# output.net
KiCad netlist of a schematic drawn in Altium Designer
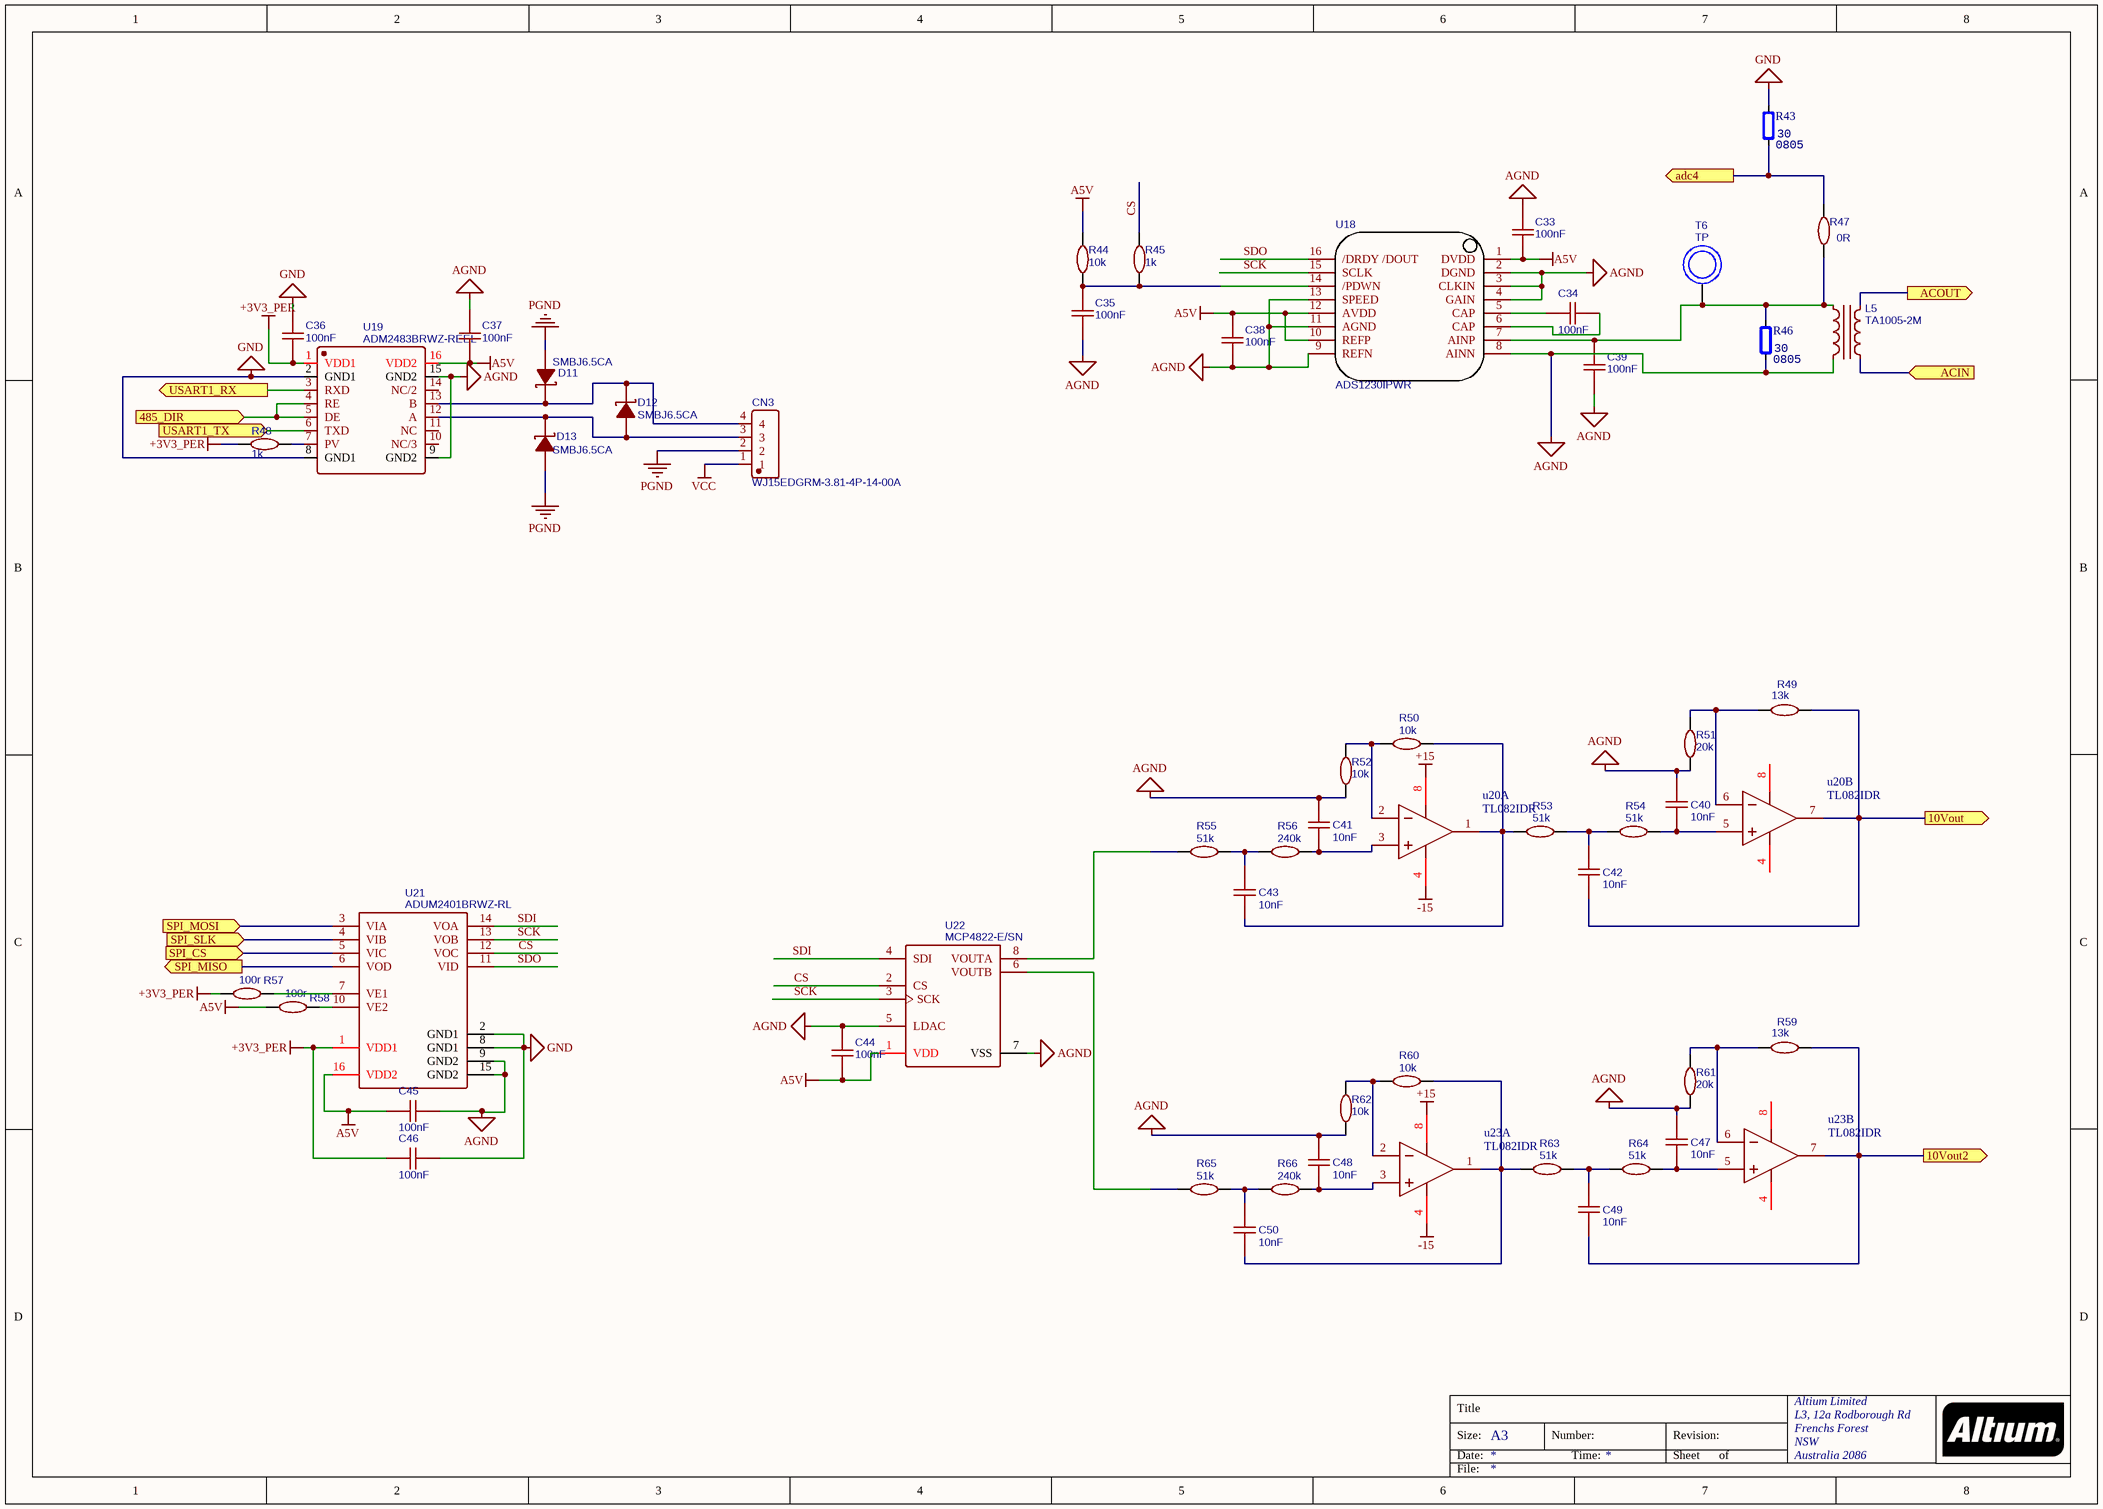
[diagram p0: output.SchDoc]

(export (version "E")
  (design (tool "Eeschema 10.0.6"))
  (components
    (comp (ref "C33")
      (value "100nF")
      (footprint "0603 - cap")
      (fields (field (name "BOM_MANUFACTURER PART") "CC0603KRX7R9BB104"))
      (libsource (lib "") (part "root_3___1"))
    )
    (comp (ref "C34")
      (value "100nF")
      (footprint "0603 - cap")
      (fields (field (name "BOM_MANUFACTURER PART") "CC0603KRX7R9BB104"))
      (libsource (lib "") (part "root_0___4"))
    )
    (comp (ref "C35")
      (value "100nF")
      (footprint "0603 - cap")
      (fields (field (name "BOM_MANUFACTURER PART") "CC0603KRX7R9BB104"))
      (libsource (lib "") (part "root_3___1"))
    )
    (comp (ref "C36")
      (value "100nF")
      (footprint "0603 - cap")
      (fields (field (name "BOM_MANUFACTURER PART") "CC0603KRX7R9BB104"))
      (libsource (lib "") (part "root_3___1"))
    )
    (comp (ref "C37")
      (value "100nF")
      (footprint "0603 - cap")
      (fields (field (name "BOM_MANUFACTURER PART") "CC0603KRX7R9BB104"))
      (libsource (lib "") (part "root_3___1"))
    )
    (comp (ref "C38")
      (value "100nF")
      (footprint "0603 - cap")
      (fields (field (name "BOM_MANUFACTURER PART") "CC0603KRX7R9BB104"))
      (libsource (lib "") (part "root_3___1"))
    )
    (comp (ref "C39")
      (value "100nF")
      (footprint "0603 - cap")
      (fields (field (name "BOM_MANUFACTURER PART") "CC0603KRX7R9BB104"))
      (libsource (lib "") (part "root_3___1"))
    )
    (comp (ref "C40")
      (value "10nF")
      (footprint "0603 - cap")
      (fields (field (name "BOM_MANUFACTURER PART") "CC0603KRX7R9BB104"))
      (libsource (lib "") (part "root_1___1"))
    )
    (comp (ref "C41")
      (value "10nF")
      (footprint "0603 - cap")
      (fields (field (name "BOM_MANUFACTURER PART") "CC0603KRX7R9BB104"))
      (libsource (lib "") (part "root_1___1"))
    )
    (comp (ref "C42")
      (value "10nF")
      (footprint "0603 - cap")
      (fields (field (name "BOM_MANUFACTURER PART") "CC0603KRX7R9BB104"))
      (libsource (lib "") (part "root_1___1"))
    )
    (comp (ref "C43")
      (value "10nF")
      (footprint "0603 - cap")
      (fields (field (name "BOM_MANUFACTURER PART") "CC0603KRX7R9BB104"))
      (libsource (lib "") (part "root_1___1"))
    )
    (comp (ref "C44")
      (value "100nF")
      (footprint "0603 - cap")
      (fields (field (name "BOM_MANUFACTURER PART") "CC0603KRX7R9BB104"))
      (libsource (lib "") (part "root_3___1"))
    )
    (comp (ref "C45")
      (value "100nF")
      (footprint "0603 - cap")
      (fields (field (name "BOM_MANUFACTURER PART") "CC0603KRX7R9BB104"))
      (libsource (lib "altium-import") (part "root_2__"))
    )
    (comp (ref "C46")
      (value "100nF")
      (footprint "0603 - cap")
      (fields (field (name "BOM_MANUFACTURER PART") "CC0603KRX7R9BB104"))
      (libsource (lib "altium-import") (part "root_2__"))
    )
    (comp (ref "C47")
      (value "10nF")
      (footprint "0603 - cap")
      (fields (field (name "BOM_MANUFACTURER PART") "CC0603KRX7R9BB104"))
      (libsource (lib "") (part "root_1___1"))
    )
    (comp (ref "C48")
      (value "10nF")
      (footprint "0603 - cap")
      (fields (field (name "BOM_MANUFACTURER PART") "CC0603KRX7R9BB104"))
      (libsource (lib "") (part "root_1___1"))
    )
    (comp (ref "C49")
      (value "10nF")
      (footprint "0603 - cap")
      (fields (field (name "BOM_MANUFACTURER PART") "CC0603KRX7R9BB104"))
      (libsource (lib "") (part "root_1___1"))
    )
    (comp (ref "C50")
      (value "10nF")
      (footprint "0603 - cap")
      (fields (field (name "BOM_MANUFACTURER PART") "CC0603KRX7R9BB104"))
      (libsource (lib "") (part "root_1___1"))
    )
    (comp (ref "CN3")
      (value "WJ15EDGRM-3.81-4P-14-00A")
      (footprint "3.84-4p")
      (fields (field (name "CONTRIBUTOR") "LCSC"))
      (libsource (lib "altium-import") (part "root_2_mirrored__"))
    )
    (comp (ref "D11")
      (value "SMBJ6.5CA")
      (footprint "SMB(DO-214AA)")
      (libsource (lib "") (part "root_1___2"))
    )
    (comp (ref "D12")
      (value "SMBJ6.5CA")
      (footprint "SMB(DO-214AA)")
      (libsource (lib "altium-import") (part "root_3__"))
    )
    (comp (ref "D13")
      (value "SMBJ6.5CA")
      (footprint "SMB(DO-214AA)")
      (libsource (lib "altium-import") (part "root_3__"))
    )
    (comp (ref "L5") (value "TA1005-2M") (footprint "TA1005-2M") (libsource (lib "") (part "root_3___2")))
    (comp (ref "R43")
      (value "30")
      (footprint "PCB_PassiveRes:RES_0805")
      (description "Resistor")
      (fields (field (name "TYPE") "0805") (field (name "Comment") "R0805"))
      (libsource (lib "SCH_Passive") (part "Res_0805"))
    )
    (comp (ref "R44")
      (value "10k")
      (footprint "0603-res")
      (fields (field (name "BOM_MANUFACTURER PART") "0603WAF1001T5E"))
      (libsource (lib "altium-import") (part "root_1__"))
    )
    (comp (ref "R45")
      (value "1k")
      (footprint "0603-res")
      (fields (field (name "BOM_MANUFACTURER PART") "0603WAF1001T5E"))
      (libsource (lib "altium-import") (part "root_1__"))
    )
    (comp (ref "R46")
      (value "30")
      (footprint "PCB_PassiveRes:RES_0805")
      (description "Resistor")
      (fields (field (name "TYPE") "0805") (field (name "Comment") "R0805"))
      (libsource (lib "SCH_Passive") (part "Res_0805"))
    )
    (comp (ref "R47")
      (value "0R")
      (footprint "0603-res")
      (fields (field (name "BOM_MANUFACTURER PART") "0603WAF1001T5E"))
      (libsource (lib "altium-import") (part "root_1__"))
    )
    (comp (ref "R48")
      (value "1k")
      (footprint "0603-res")
      (fields (field (name "BOM_MANUFACTURER PART") "0603WAF1001T5E"))
      (libsource (lib "altium-import") (part "root_0__"))
    )
    (comp (ref "R49")
      (value "13k")
      (footprint "0603-res")
      (fields (field (name "BOM_MANUFACTURER PART") "0603WAF1001T5E"))
      (libsource (lib "altium-import") (part "root_0__"))
    )
    (comp (ref "R50")
      (value "10k")
      (footprint "0603-res")
      (fields (field (name "BOM_MANUFACTURER PART") "0603WAF1001T5E"))
      (libsource (lib "altium-import") (part "root_0__"))
    )
    (comp (ref "R51")
      (value "20k")
      (footprint "0603-res")
      (fields (field (name "BOM_MANUFACTURER PART") "0603WAF1001T5E"))
      (libsource (lib "altium-import") (part "root_1__"))
    )
    (comp (ref "R52")
      (value "10k")
      (footprint "0603-res")
      (fields (field (name "BOM_MANUFACTURER PART") "0603WAF1001T5E"))
      (libsource (lib "altium-import") (part "root_1__"))
    )
    (comp (ref "R53")
      (value "51k")
      (footprint "0603-res")
      (fields (field (name "BOM_MANUFACTURER PART") "0603WAF1001T5E"))
      (libsource (lib "altium-import") (part "root_0__"))
    )
    (comp (ref "R54")
      (value "51k")
      (footprint "0603-res")
      (fields (field (name "BOM_MANUFACTURER PART") "0603WAF1001T5E"))
      (libsource (lib "altium-import") (part "root_0__"))
    )
    (comp (ref "R55")
      (value "51k")
      (footprint "0603-res")
      (fields (field (name "BOM_MANUFACTURER PART") "0603WAF1001T5E"))
      (libsource (lib "altium-import") (part "root_0__"))
    )
    (comp (ref "R56")
      (value "240k")
      (footprint "0603-res")
      (fields (field (name "BOM_MANUFACTURER PART") "0603WAF1001T5E"))
      (libsource (lib "altium-import") (part "root_0__"))
    )
    (comp (ref "R57")
      (value "100r")
      (footprint "0603-res")
      (fields (field (name "BOM_MANUFACTURER PART") "0603WAF1001T5E"))
      (libsource (lib "altium-import") (part "root_0__"))
    )
    (comp (ref "R58")
      (value "100r")
      (footprint "0603-res")
      (fields (field (name "BOM_MANUFACTURER PART") "0603WAF1001T5E"))
      (libsource (lib "altium-import") (part "root_0__"))
    )
    (comp (ref "R59")
      (value "13k")
      (footprint "0603-res")
      (fields (field (name "BOM_MANUFACTURER PART") "0603WAF1001T5E"))
      (libsource (lib "altium-import") (part "root_0__"))
    )
    (comp (ref "R60")
      (value "10k")
      (footprint "0603-res")
      (fields (field (name "BOM_MANUFACTURER PART") "0603WAF1001T5E"))
      (libsource (lib "altium-import") (part "root_0__"))
    )
    (comp (ref "R61")
      (value "20k")
      (footprint "0603-res")
      (fields (field (name "BOM_MANUFACTURER PART") "0603WAF1001T5E"))
      (libsource (lib "altium-import") (part "root_1__"))
    )
    (comp (ref "R62")
      (value "10k")
      (footprint "0603-res")
      (fields (field (name "BOM_MANUFACTURER PART") "0603WAF1001T5E"))
      (libsource (lib "altium-import") (part "root_1__"))
    )
    (comp (ref "R63")
      (value "51k")
      (footprint "0603-res")
      (fields (field (name "BOM_MANUFACTURER PART") "0603WAF1001T5E"))
      (libsource (lib "altium-import") (part "root_0__"))
    )
    (comp (ref "R64")
      (value "51k")
      (footprint "0603-res")
      (fields (field (name "BOM_MANUFACTURER PART") "0603WAF1001T5E"))
      (libsource (lib "altium-import") (part "root_0__"))
    )
    (comp (ref "R65")
      (value "51k")
      (footprint "0603-res")
      (fields (field (name "BOM_MANUFACTURER PART") "0603WAF1001T5E"))
      (libsource (lib "altium-import") (part "root_0__"))
    )
    (comp (ref "R66")
      (value "240k")
      (footprint "0603-res")
      (fields (field (name "BOM_MANUFACTURER PART") "0603WAF1001T5E"))
      (libsource (lib "altium-import") (part "root_0__"))
    )
    (comp (ref "T6")
      (value "TP")
      (footprint "tp")
      (fields (field (name "BOM_MANUFACTURER PART") "?"))
      (libsource (lib "") (part "root_0___5"))
    )
    (comp (ref "U18")
      (value "ADS1230IPWR")
      (footprint "TSSOP-16")
      (libsource (lib "altium-import") (part "root_0_mirrored__"))
    )
    (comp (ref "U19")
      (value "ADM2483BRWZ-REEL")
      (footprint "SOIC-16_300MIL")
      (libsource (lib "") (part "root_0___3"))
    )
    (comp (ref "u20")
      (value "TL082IDR")
      (footprint "SOIC-8_150MIL")
      (libsource (lib "TcpControl_1") (part "tl802t"))
    )
    (comp (ref "U21")
      (value "ADUM2401BRWZ-RL")
      (footprint "SOIC-16_300MIL")
      (libsource (lib "") (part "root_0___1"))
    )
    (comp (ref "U22")
      (value "MCP4822-E/SN")
      (footprint "SOIC-8_150MIL")
      (libsource (lib "") (part "root_0___2"))
    )
    (comp (ref "u23")
      (value "TL082IDR")
      (footprint "SOIC-8_150MIL")
      (libsource (lib "TcpControl_1") (part "tl802t"))
    )
  )
  (nets
    (net (code "1") (name "+3V3_PER") (class "Default")
      (node (ref "C36") (pin "2") (pinfunction "2_2") (pintype "passive"))
      (node (ref "C46") (pin "2") (pinfunction "2_2") (pintype "passive"))
      (node (ref "R48") (pin "1") (pinfunction "1_1") (pintype "passive"))
      (node (ref "R57") (pin "1") (pinfunction "1_1") (pintype "passive"))
      (node (ref "U19") (pin "1") (pinfunction "VDD1_1") (pintype "passive"))
      (node (ref "U21") (pin "1") (pinfunction "VDD1_1") (pintype "passive"))
    )
    (net (code "2") (name "+15") (class "Default")
      (node (ref "u20") (pin "8") (pinfunction "VCC+_8") (pintype "passive"))
      (node (ref "u23") (pin "8") (pinfunction "VCC+_8") (pintype "passive"))
    )
    (net (code "3") (name "-15") (class "Default")
      (node (ref "u20") (pin "4") (pinfunction "VCC-_4") (pintype "passive"))
      (node (ref "u23") (pin "4") (pinfunction "VCC-_4") (pintype "passive"))
    )
    (net (code "4") (name "/10Vout") (class "Default")
      (node (ref "C42") (pin "1") (pinfunction "1_1") (pintype "passive"))
      (node (ref "R49") (pin "2") (pinfunction "2_2") (pintype "passive"))
      (node (ref "u20") (pin "7") (pinfunction "OUT2_7") (pintype "passive"))
    )
    (net (code "5") (name "/10Vout2") (class "Default")
      (node (ref "C49") (pin "1") (pinfunction "1_1") (pintype "passive"))
      (node (ref "R59") (pin "2") (pinfunction "2_2") (pintype "passive"))
      (node (ref "u23") (pin "7") (pinfunction "OUT2_7") (pintype "passive"))
    )
    (net (code "6") (name "/485_DIR") (class "Default")
      (node (ref "U19") (pin "4") (pinfunction "RE_4") (pintype "passive"))
      (node (ref "U19") (pin "5") (pinfunction "DE_5") (pintype "passive"))
    )
    (net (code "7") (name "/ACIN") (class "Default")
      (node (ref "L5") (pin "1") (pinfunction "1_1") (pintype "passive"))
    )
    (net (code "8") (name "/ACOUT") (class "Default")
      (node (ref "L5") (pin "2") (pinfunction "2_2") (pintype "passive"))
    )
    (net (code "9") (name "/CS") (class "Default")
      (node (ref "R45") (pin "2") (pinfunction "2_2") (pintype "passive"))
      (node (ref "U21") (pin "12") (pinfunction "VOC_12") (pintype "passive"))
      (node (ref "U22") (pin "2") (pinfunction "CS_2") (pintype "passive"))
    )
    (net (code "10") (name "/SCK") (class "Default")
      (node (ref "U18") (pin "15") (pinfunction "SCLK_15") (pintype "passive"))
      (node (ref "U21") (pin "13") (pinfunction "VOB_13") (pintype "passive"))
      (node (ref "U22") (pin "3") (pinfunction "SCK_3") (pintype "passive"))
    )
    (net (code "11") (name "/SDI") (class "Default")
      (node (ref "U21") (pin "14") (pinfunction "VOA_14") (pintype "passive"))
      (node (ref "U22") (pin "4") (pinfunction "SDI_4") (pintype "passive"))
    )
    (net (code "12") (name "/SDO") (class "Default")
      (node (ref "U18") (pin "16") (pinfunction "/DRDY_/DOUT_16") (pintype "passive"))
      (node (ref "U21") (pin "11") (pinfunction "VID_11") (pintype "passive"))
    )
    (net (code "13") (name "/SPI_CS") (class "Default")
      (node (ref "U21") (pin "5") (pinfunction "VIC_5") (pintype "passive"))
    )
    (net (code "14") (name "/SPI_MISO") (class "Default")
      (node (ref "U21") (pin "6") (pinfunction "VOD_6") (pintype "passive"))
    )
    (net (code "15") (name "/SPI_MOSI") (class "Default")
      (node (ref "U21") (pin "3") (pinfunction "VIA_3") (pintype "passive"))
    )
    (net (code "16") (name "/SPI_SLK") (class "Default")
      (node (ref "U21") (pin "4") (pinfunction "VIB_4") (pintype "passive"))
    )
    (net (code "17") (name "/USART1_RX") (class "Default")
      (node (ref "U19") (pin "3") (pinfunction "RXD_3") (pintype "passive"))
    )
    (net (code "18") (name "/USART1_TX") (class "Default")
      (node (ref "U19") (pin "6") (pinfunction "TXD_6") (pintype "passive"))
    )
    (net (code "19") (name "/adc4") (class "Default")
      (node (ref "R43") (pin "1") (pinfunction "1_1") (pintype "passive"))
      (node (ref "R47") (pin "2") (pinfunction "2_2") (pintype "passive"))
    )
    (net (code "20") (name "A5V") (class "Default")
      (node (ref "C33") (pin "2") (pinfunction "2_2") (pintype "passive"))
      (node (ref "C37") (pin "2") (pinfunction "2_2") (pintype "passive"))
      (node (ref "C38") (pin "1") (pinfunction "1_1") (pintype "passive"))
      (node (ref "C44") (pin "2") (pinfunction "2_2") (pintype "passive"))
      (node (ref "C45") (pin "2") (pinfunction "2_2") (pintype "passive"))
      (node (ref "R44") (pin "2") (pinfunction "2_2") (pintype "passive"))
      (node (ref "R58") (pin "1") (pinfunction "1_1") (pintype "passive"))
      (node (ref "U18") (pin "1") (pinfunction "DVDD_1") (pintype "passive"))
      (node (ref "U18") (pin "10") (pinfunction "REFP_10") (pintype "passive"))
      (node (ref "U18") (pin "12") (pinfunction "AVDD_12") (pintype "passive"))
      (node (ref "U19") (pin "16") (pinfunction "VDD2_16") (pintype "passive"))
      (node (ref "U21") (pin "16") (pinfunction "VDD2_16") (pintype "passive"))
      (node (ref "U22") (pin "1") (pinfunction "VDD_1") (pintype "passive"))
    )
    (net (code "21") (name "AGND") (class "Default")
      (node (ref "C33") (pin "1") (pinfunction "1_1") (pintype "passive"))
      (node (ref "C35") (pin "2") (pinfunction "2_2") (pintype "passive"))
      (node (ref "C37") (pin "1") (pinfunction "1_1") (pintype "passive"))
      (node (ref "C38") (pin "2") (pinfunction "2_2") (pintype "passive"))
      (node (ref "C39") (pin "2") (pinfunction "2_2") (pintype "passive"))
      (node (ref "C40") (pin "2") (pinfunction "2_2") (pintype "passive"))
      (node (ref "C41") (pin "2") (pinfunction "2_2") (pintype "passive"))
      (node (ref "C44") (pin "1") (pinfunction "1_1") (pintype "passive"))
      (node (ref "C45") (pin "1") (pinfunction "1_1") (pintype "passive"))
      (node (ref "C47") (pin "2") (pinfunction "2_2") (pintype "passive"))
      (node (ref "C48") (pin "2") (pinfunction "2_2") (pintype "passive"))
      (node (ref "L5") (pin "4") (pinfunction "4_4") (pintype "passive"))
      (node (ref "R46") (pin "1") (pinfunction "1_1") (pintype "passive"))
      (node (ref "R51") (pin "1") (pinfunction "1_1") (pintype "passive"))
      (node (ref "R52") (pin "1") (pinfunction "1_1") (pintype "passive"))
      (node (ref "R61") (pin "1") (pinfunction "1_1") (pintype "passive"))
      (node (ref "R62") (pin "1") (pinfunction "1_1") (pintype "passive"))
      (node (ref "U18") (pin "11") (pinfunction "AGND_11") (pintype "passive"))
      (node (ref "U18") (pin "13") (pinfunction "SPEED_13") (pintype "passive"))
      (node (ref "U18") (pin "2") (pinfunction "DGND_2") (pintype "passive"))
      (node (ref "U18") (pin "3") (pinfunction "CLKIN_3") (pintype "passive"))
      (node (ref "U18") (pin "4") (pinfunction "GAIN_4") (pintype "passive"))
      (node (ref "U18") (pin "8") (pinfunction "AINN_8") (pintype "passive"))
      (node (ref "U18") (pin "9") (pinfunction "REFN_9") (pintype "passive"))
      (node (ref "U19") (pin "15") (pinfunction "GND2_15") (pintype "passive"))
      (node (ref "U19") (pin "9") (pinfunction "GND2_9") (pintype "passive"))
      (node (ref "U21") (pin "15") (pinfunction "GND2_15") (pintype "passive"))
      (node (ref "U21") (pin "9") (pinfunction "GND2_9") (pintype "passive"))
      (node (ref "U22") (pin "5") (pinfunction "LDAC_5") (pintype "passive"))
      (node (ref "U22") (pin "7") (pinfunction "VSS_7") (pintype "passive"))
    )
    (net (code "22") (name "GND") (class "Default")
      (node (ref "C36") (pin "1") (pinfunction "1_1") (pintype "passive"))
      (node (ref "C46") (pin "1") (pinfunction "1_1") (pintype "passive"))
      (node (ref "R43") (pin "2") (pinfunction "2_2") (pintype "passive"))
      (node (ref "U19") (pin "2") (pinfunction "GND1_2") (pintype "passive"))
      (node (ref "U19") (pin "8") (pinfunction "GND1_8") (pintype "passive"))
      (node (ref "U21") (pin "2") (pinfunction "GND1_2") (pintype "passive"))
      (node (ref "U21") (pin "8") (pinfunction "GND1_8") (pintype "passive"))
    )
    (net (code "23") (name "Net-(C34-Pad1)") (class "Default")
      (node (ref "C34") (pin "1") (pinfunction "1_1") (pintype "passive"))
      (node (ref "U18") (pin "5") (pinfunction "CAP_5") (pintype "passive"))
    )
    (net (code "24") (name "Net-(C34-Pad2)") (class "Default")
      (node (ref "C34") (pin "2") (pinfunction "2_2") (pintype "passive"))
      (node (ref "U18") (pin "6") (pinfunction "CAP_6") (pintype "passive"))
    )
    (net (code "25") (name "Net-(C42-Pad2)") (class "Default")
      (node (ref "C42") (pin "2") (pinfunction "2_2") (pintype "passive"))
      (node (ref "R53") (pin "2") (pinfunction "2_2") (pintype "passive"))
      (node (ref "R54") (pin "1") (pinfunction "1_1") (pintype "passive"))
    )
    (net (code "26") (name "Net-(C43-Pad2)") (class "Default")
      (node (ref "C43") (pin "2") (pinfunction "2_2") (pintype "passive"))
      (node (ref "R55") (pin "2") (pinfunction "2_2") (pintype "passive"))
      (node (ref "R56") (pin "1") (pinfunction "1_1") (pintype "passive"))
    )
    (net (code "27") (name "Net-(C49-Pad2)") (class "Default")
      (node (ref "C49") (pin "2") (pinfunction "2_2") (pintype "passive"))
      (node (ref "R63") (pin "2") (pinfunction "2_2") (pintype "passive"))
      (node (ref "R64") (pin "1") (pinfunction "1_1") (pintype "passive"))
    )
    (net (code "28") (name "Net-(C50-Pad2)") (class "Default")
      (node (ref "C50") (pin "2") (pinfunction "2_2") (pintype "passive"))
      (node (ref "R65") (pin "2") (pinfunction "2_2") (pintype "passive"))
      (node (ref "R66") (pin "1") (pinfunction "1_1") (pintype "passive"))
    )
    (net (code "29") (name "Net-(U18-AINP)") (class "Default")
      (node (ref "C39") (pin "1") (pinfunction "1_1") (pintype "passive"))
      (node (ref "L5") (pin "3") (pinfunction "3_3") (pintype "passive"))
      (node (ref "R46") (pin "2") (pinfunction "2_2") (pintype "passive"))
      (node (ref "R47") (pin "1") (pinfunction "1_1") (pintype "passive"))
      (node (ref "T6") (pin "1") (pintype "passive"))
      (node (ref "U18") (pin "7") (pinfunction "AINP_7") (pintype "passive"))
    )
    (net (code "30") (name "Net-(U18-{slash}PDWN)") (class "Default")
      (node (ref "C35") (pin "1") (pinfunction "1_1") (pintype "passive"))
      (node (ref "R44") (pin "1") (pinfunction "1_1") (pintype "passive"))
      (node (ref "R45") (pin "1") (pinfunction "1_1") (pintype "passive"))
      (node (ref "U18") (pin "14") (pinfunction "/PDWN_14") (pintype "passive"))
    )
    (net (code "31") (name "Net-(U19-A)") (class "Default")
      (node (ref "CN3") (pin "3") (pinfunction "3_3") (pintype "passive"))
      (node (ref "D12") (pin "1") (pinfunction "1_1") (pintype "passive"))
      (node (ref "D13") (pin "2") (pinfunction "2_2") (pintype "passive"))
      (node (ref "U19") (pin "12") (pinfunction "A_12") (pintype "passive"))
    )
    (net (code "32") (name "Net-(U19-B)") (class "Default")
      (node (ref "CN3") (pin "4") (pinfunction "4_4") (pintype "passive"))
      (node (ref "D11") (pin "2") (pinfunction "2_2") (pintype "passive"))
      (node (ref "D12") (pin "2") (pinfunction "2_2") (pintype "passive"))
      (node (ref "U19") (pin "13") (pinfunction "B_13") (pintype "passive"))
    )
    (net (code "33") (name "Net-(U19-PV)") (class "Default")
      (node (ref "R48") (pin "2") (pinfunction "2_2") (pintype "passive"))
      (node (ref "U19") (pin "7") (pinfunction "PV_7") (pintype "passive"))
    )
    (net (code "34") (name "Net-(U21-VE1)") (class "Default")
      (node (ref "R57") (pin "2") (pinfunction "2_2") (pintype "passive"))
      (node (ref "U21") (pin "7") (pinfunction "VE1_7") (pintype "passive"))
    )
    (net (code "35") (name "Net-(U21-VE2)") (class "Default")
      (node (ref "R58") (pin "2") (pinfunction "2_2") (pintype "passive"))
      (node (ref "U21") (pin "10") (pinfunction "VE2_10") (pintype "passive"))
    )
    (net (code "36") (name "Net-(U22-VOUTA)") (class "Default")
      (node (ref "R55") (pin "1") (pinfunction "1_1") (pintype "passive"))
      (node (ref "U22") (pin "8") (pinfunction "VOUTA_8") (pintype "passive"))
    )
    (net (code "37") (name "Net-(U22-VOUTB)") (class "Default")
      (node (ref "R65") (pin "1") (pinfunction "1_1") (pintype "passive"))
      (node (ref "U22") (pin "6") (pinfunction "VOUTB_6") (pintype "passive"))
    )
    (net (code "38") (name "Net-(u20A-IN1+)") (class "Default")
      (node (ref "C41") (pin "1") (pinfunction "1_1") (pintype "passive"))
      (node (ref "R56") (pin "2") (pinfunction "2_2") (pintype "passive"))
      (node (ref "u20") (pin "3") (pinfunction "IN1+_3") (pintype "passive"))
    )
    (net (code "39") (name "Net-(u20A-IN1-)") (class "Default")
      (node (ref "R50") (pin "1") (pinfunction "1_1") (pintype "passive"))
      (node (ref "R52") (pin "2") (pinfunction "2_2") (pintype "passive"))
      (node (ref "u20") (pin "2") (pinfunction "IN1-_2") (pintype "passive"))
    )
    (net (code "40") (name "Net-(u20A-OUT1)") (class "Default")
      (node (ref "C43") (pin "1") (pinfunction "1_1") (pintype "passive"))
      (node (ref "R50") (pin "2") (pinfunction "2_2") (pintype "passive"))
      (node (ref "R53") (pin "1") (pinfunction "1_1") (pintype "passive"))
      (node (ref "u20") (pin "1") (pinfunction "OUT1_1") (pintype "passive"))
    )
    (net (code "41") (name "Net-(u20B-IN2+)") (class "Default")
      (node (ref "C40") (pin "1") (pinfunction "1_1") (pintype "passive"))
      (node (ref "R54") (pin "2") (pinfunction "2_2") (pintype "passive"))
      (node (ref "u20") (pin "5") (pinfunction "IN2+_5") (pintype "passive"))
    )
    (net (code "42") (name "Net-(u20B-IN2-)") (class "Default")
      (node (ref "R49") (pin "1") (pinfunction "1_1") (pintype "passive"))
      (node (ref "R51") (pin "2") (pinfunction "2_2") (pintype "passive"))
      (node (ref "u20") (pin "6") (pinfunction "IN2-_6") (pintype "passive"))
    )
    (net (code "43") (name "Net-(u23A-IN1+)") (class "Default")
      (node (ref "C48") (pin "1") (pinfunction "1_1") (pintype "passive"))
      (node (ref "R66") (pin "2") (pinfunction "2_2") (pintype "passive"))
      (node (ref "u23") (pin "3") (pinfunction "IN1+_3") (pintype "passive"))
    )
    (net (code "44") (name "Net-(u23A-IN1-)") (class "Default")
      (node (ref "R60") (pin "1") (pinfunction "1_1") (pintype "passive"))
      (node (ref "R62") (pin "2") (pinfunction "2_2") (pintype "passive"))
      (node (ref "u23") (pin "2") (pinfunction "IN1-_2") (pintype "passive"))
    )
    (net (code "45") (name "Net-(u23A-OUT1)") (class "Default")
      (node (ref "C50") (pin "1") (pinfunction "1_1") (pintype "passive"))
      (node (ref "R60") (pin "2") (pinfunction "2_2") (pintype "passive"))
      (node (ref "R63") (pin "1") (pinfunction "1_1") (pintype "passive"))
      (node (ref "u23") (pin "1") (pinfunction "OUT1_1") (pintype "passive"))
    )
    (net (code "46") (name "Net-(u23B-IN2+)") (class "Default")
      (node (ref "C47") (pin "1") (pinfunction "1_1") (pintype "passive"))
      (node (ref "R64") (pin "2") (pinfunction "2_2") (pintype "passive"))
      (node (ref "u23") (pin "5") (pinfunction "IN2+_5") (pintype "passive"))
    )
    (net (code "47") (name "Net-(u23B-IN2-)") (class "Default")
      (node (ref "R59") (pin "1") (pinfunction "1_1") (pintype "passive"))
      (node (ref "R61") (pin "2") (pinfunction "2_2") (pintype "passive"))
      (node (ref "u23") (pin "6") (pinfunction "IN2-_6") (pintype "passive"))
    )
    (net (code "48") (name "PGND") (class "Default")
      (node (ref "CN3") (pin "2") (pinfunction "2_2") (pintype "passive"))
      (node (ref "D11") (pin "1") (pinfunction "1_1") (pintype "passive"))
      (node (ref "D13") (pin "1") (pinfunction "1_1") (pintype "passive"))
    )
    (net (code "49") (name "VCC") (class "Default")
      (node (ref "CN3") (pin "1") (pinfunction "1_1") (pintype "passive"))
    )
    (net (code "50") (name "unconnected-(U19-NC-Pad11)") (class "Default")
      (node (ref "U19") (pin "11") (pinfunction "NC_11") (pintype "passive"))
    )
    (net (code "51") (name "unconnected-(U19-NC{slash}2-Pad14)") (class "Default")
      (node (ref "U19") (pin "14") (pinfunction "NC/2_14") (pintype "passive"))
    )
    (net (code "52") (name "unconnected-(U19-NC{slash}3-Pad10)") (class "Default")
      (node (ref "U19") (pin "10") (pinfunction "NC/3_10") (pintype "passive"))
    )
    (net (code "53") (name "unconnected-(u20B-VCC+-Pad8)") (class "Default")
      (node (ref "u20") (pin "8") (pinfunction "VCC+_8") (pintype "passive"))
    )
    (net (code "54") (name "unconnected-(u20B-VCC--Pad4)") (class "Default")
      (node (ref "u20") (pin "4") (pinfunction "VCC-_4") (pintype "passive"))
    )
    (net (code "55") (name "unconnected-(u23B-VCC+-Pad8)") (class "Default")
      (node (ref "u23") (pin "8") (pinfunction "VCC+_8") (pintype "passive"))
    )
    (net (code "56") (name "unconnected-(u23B-VCC--Pad4)") (class "Default")
      (node (ref "u23") (pin "4") (pinfunction "VCC-_4") (pintype "passive"))
    )
  )
)
